# OLD_Motors.net
KiCad netlist of a schematic drawn in Altium Designer
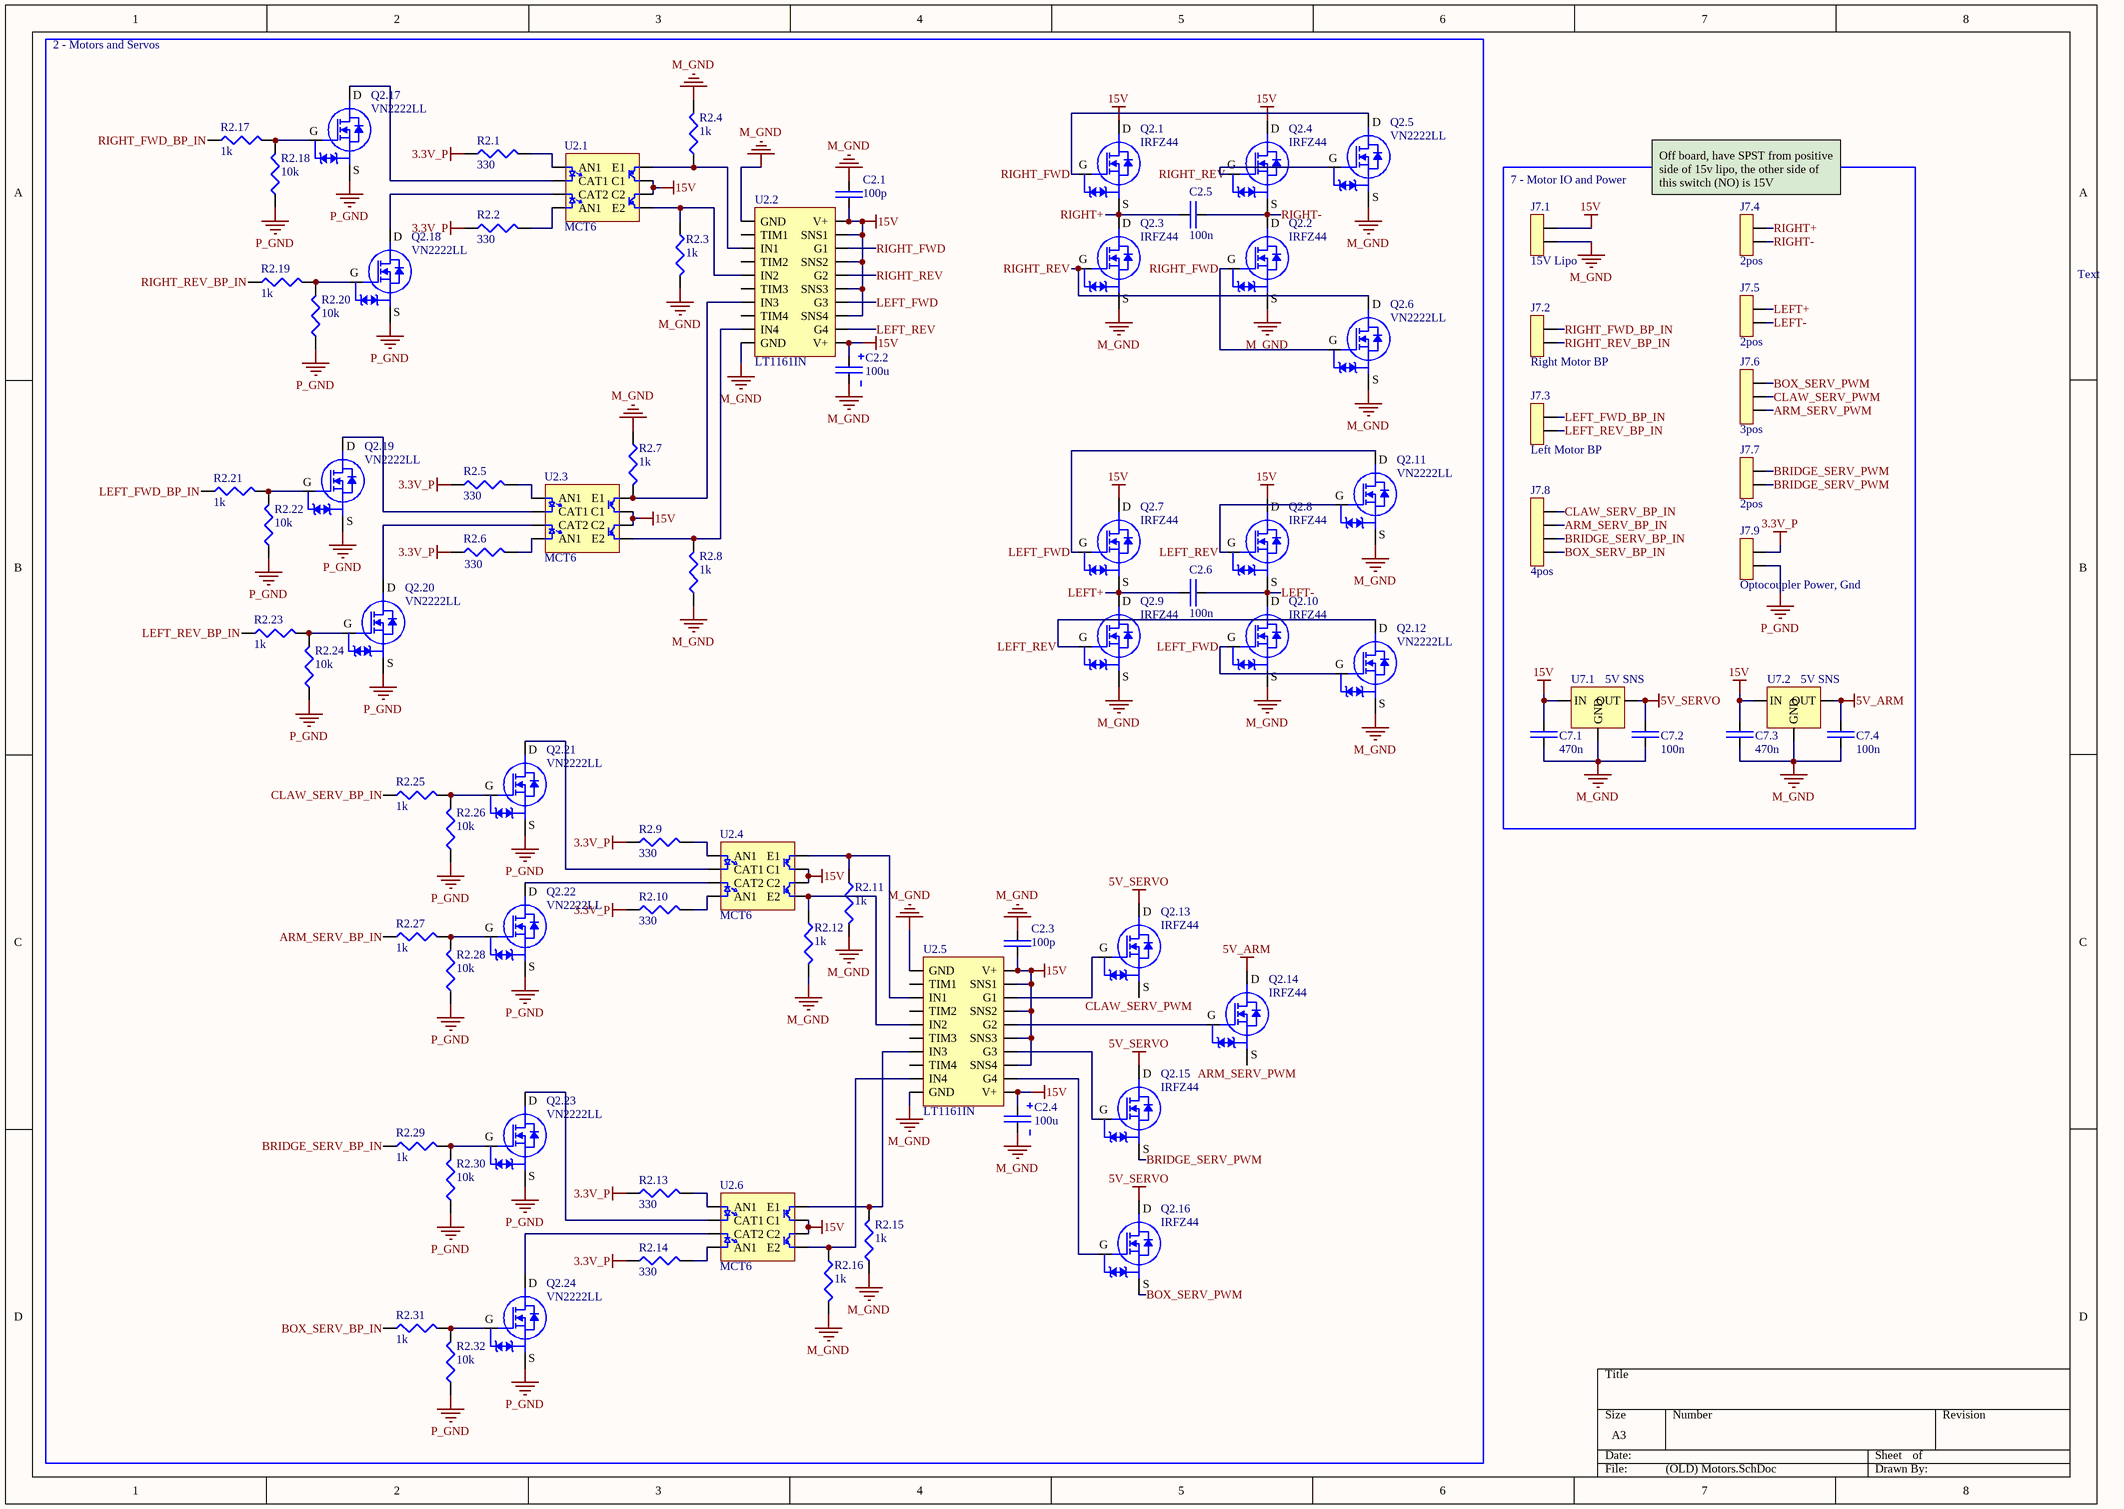
[diagram p0: (OLD) Motors.SchDoc]

(export (version "E")
  (design (tool "Eeschema 10.0.6"))
  (components
    (comp (ref "C2.1")
      (value "100p")
      (footprint "Non Polarized Cap")
      (libsource (lib "SPICEBot_SchLib") (part "Cap_Generic"))
    )
    (comp (ref "C2.2")
      (value "100u")
      (footprint "Polarized Cap")
      (libsource (lib "SPICEBot_SchLib") (part "Polarized Cap"))
    )
    (comp (ref "C2.3")
      (value "100p")
      (footprint "Non Polarized Cap")
      (libsource (lib "SPICEBot_SchLib") (part "Cap_Generic"))
    )
    (comp (ref "C2.4")
      (value "100u")
      (footprint "Polarized Cap")
      (libsource (lib "SPICEBot_SchLib") (part "Polarized Cap"))
    )
    (comp (ref "C2.5")
      (value "100n")
      (footprint "Non Polarized Cap")
      (libsource (lib "SPICEBot_SchLib") (part "Cap_Generic"))
    )
    (comp (ref "C2.6")
      (value "100n")
      (footprint "Non Polarized Cap")
      (libsource (lib "SPICEBot_SchLib") (part "Cap_Generic"))
    )
    (comp (ref "C7.1")
      (value "470n")
      (footprint "Non Polarized Cap")
      (libsource (lib "SPICEBot_SchLib") (part "Cap_Generic"))
    )
    (comp (ref "C7.2")
      (value "100n")
      (footprint "Non Polarized Cap")
      (libsource (lib "SPICEBot_SchLib") (part "Cap_Generic"))
    )
    (comp (ref "C7.3")
      (value "470n")
      (footprint "Non Polarized Cap")
      (libsource (lib "SPICEBot_SchLib") (part "Cap_Generic"))
    )
    (comp (ref "C7.4")
      (value "100n")
      (footprint "Non Polarized Cap")
      (libsource (lib "SPICEBot_SchLib") (part "Cap_Generic"))
    )
    (comp (ref "J7.1")
      (value "15V Lipo")
      (footprint "2pos JST")
      (description "2pos Conn JST")
      (libsource (lib "SPICEBot_SchLib") (part "2pos Conn"))
    )
    (comp (ref "J7.2")
      (value "Right Motor BP")
      (footprint "2pos JST")
      (description "2pos Conn JST")
      (libsource (lib "SPICEBot_SchLib") (part "2pos Conn"))
    )
    (comp (ref "J7.3")
      (value "Left Motor BP")
      (footprint "2pos JST")
      (description "2pos Conn JST")
      (libsource (lib "SPICEBot_SchLib") (part "2pos Conn"))
    )
    (comp (ref "J7.4")
      (value "2pos")
      (footprint "2pos JST")
      (description "2pos Conn JST")
      (libsource (lib "SPICEBot_SchLib") (part "2pos Conn"))
    )
    (comp (ref "J7.5")
      (value "2pos")
      (footprint "2pos JST")
      (description "2pos Conn JST")
      (libsource (lib "SPICEBot_SchLib") (part "2pos Conn"))
    )
    (comp (ref "J7.6")
      (value "3pos")
      (footprint "3pos JST")
      (description "3pos Conn")
      (libsource (lib "SPICEBot_SchLib") (part "3pos Conn"))
    )
    (comp (ref "J7.7")
      (value "2pos")
      (footprint "2pos JST")
      (description "2pos Conn JST")
      (libsource (lib "SPICEBot_SchLib") (part "2pos Conn"))
    )
    (comp (ref "J7.8")
      (value "4pos")
      (footprint "4Pos JST")
      (description "4pos Conn")
      (libsource (lib "SPICEBot_SchLib") (part "4pos Conn"))
    )
    (comp (ref "J7.9")
      (value "Optocoupler Power, Gnd")
      (footprint "2pos JST")
      (description "2pos Conn JST")
      (libsource (lib "SPICEBot_SchLib") (part "2pos Conn"))
    )
    (comp (ref "Q2.1")
      (value "IRFZ44")
      (footprint "TO220")
      (description "IRFZ44EPBF N-Channel 60 V 48A 110W Through Hole TO-220AB")
      (libsource (lib "SPICEBot_SchLib") (part "IRFZ44 NMOS"))
    )
    (comp (ref "Q2.2")
      (value "IRFZ44")
      (footprint "TO220")
      (description "IRFZ44EPBF N-Channel 60 V 48A 110W Through Hole TO-220AB")
      (libsource (lib "SPICEBot_SchLib") (part "IRFZ44 NMOS"))
    )
    (comp (ref "Q2.3")
      (value "IRFZ44")
      (footprint "TO220")
      (description "IRFZ44EPBF N-Channel 60 V 48A 110W Through Hole TO-220AB")
      (libsource (lib "SPICEBot_SchLib") (part "IRFZ44 NMOS"))
    )
    (comp (ref "Q2.4")
      (value "IRFZ44")
      (footprint "TO220")
      (description "IRFZ44EPBF N-Channel 60 V 48A 110W Through Hole TO-220AB")
      (libsource (lib "SPICEBot_SchLib") (part "IRFZ44 NMOS"))
    )
    (comp (ref "Q2.5")
      (value "VN2222LL")
      (footprint "VN2222LL")
      (description "VN2222LL N-Channel 60 V 150mA 400mW Through Hole TO-92 (TO-226)")
      (libsource (lib "SPICEBot_SchLib") (part "VN2222LL NMOS"))
    )
    (comp (ref "Q2.6")
      (value "VN2222LL")
      (footprint "VN2222LL")
      (description "VN2222LL N-Channel 60 V 150mA 400mW Through Hole TO-92 (TO-226)")
      (libsource (lib "SPICEBot_SchLib") (part "VN2222LL NMOS"))
    )
    (comp (ref "Q2.7")
      (value "IRFZ44")
      (footprint "TO220")
      (description "IRFZ44EPBF N-Channel 60 V 48A 110W Through Hole TO-220AB")
      (libsource (lib "SPICEBot_SchLib") (part "IRFZ44 NMOS"))
    )
    (comp (ref "Q2.8")
      (value "IRFZ44")
      (footprint "TO220")
      (description "IRFZ44EPBF N-Channel 60 V 48A 110W Through Hole TO-220AB")
      (libsource (lib "SPICEBot_SchLib") (part "IRFZ44 NMOS"))
    )
    (comp (ref "Q2.9")
      (value "IRFZ44")
      (footprint "TO220")
      (description "IRFZ44EPBF N-Channel 60 V 48A 110W Through Hole TO-220AB")
      (libsource (lib "SPICEBot_SchLib") (part "IRFZ44 NMOS"))
    )
    (comp (ref "Q2.10")
      (value "IRFZ44")
      (footprint "TO220")
      (description "IRFZ44EPBF N-Channel 60 V 48A 110W Through Hole TO-220AB")
      (libsource (lib "SPICEBot_SchLib") (part "IRFZ44 NMOS"))
    )
    (comp (ref "Q2.11")
      (value "VN2222LL")
      (footprint "VN2222LL")
      (description "VN2222LL N-Channel 60 V 150mA 400mW Through Hole TO-92 (TO-226)")
      (libsource (lib "SPICEBot_SchLib") (part "VN2222LL NMOS"))
    )
    (comp (ref "Q2.12")
      (value "VN2222LL")
      (footprint "VN2222LL")
      (description "VN2222LL N-Channel 60 V 150mA 400mW Through Hole TO-92 (TO-226)")
      (libsource (lib "SPICEBot_SchLib") (part "VN2222LL NMOS"))
    )
    (comp (ref "Q2.13")
      (value "IRFZ44")
      (footprint "TO220")
      (description "IRFZ44EPBF N-Channel 60 V 48A 110W Through Hole TO-220AB")
      (libsource (lib "SPICEBot_SchLib") (part "IRFZ44 NMOS"))
    )
    (comp (ref "Q2.14")
      (value "IRFZ44")
      (footprint "TO220")
      (description "IRFZ44EPBF N-Channel 60 V 48A 110W Through Hole TO-220AB")
      (libsource (lib "SPICEBot_SchLib") (part "IRFZ44 NMOS"))
    )
    (comp (ref "Q2.15")
      (value "IRFZ44")
      (footprint "TO220")
      (description "IRFZ44EPBF N-Channel 60 V 48A 110W Through Hole TO-220AB")
      (libsource (lib "SPICEBot_SchLib") (part "IRFZ44 NMOS"))
    )
    (comp (ref "Q2.16")
      (value "IRFZ44")
      (footprint "TO220")
      (description "IRFZ44EPBF N-Channel 60 V 48A 110W Through Hole TO-220AB")
      (libsource (lib "SPICEBot_SchLib") (part "IRFZ44 NMOS"))
    )
    (comp (ref "Q2.17")
      (value "VN2222LL")
      (footprint "VN2222LL")
      (description "VN2222LL N-Channel 60 V 150mA 400mW Through Hole TO-92 (TO-226)")
      (libsource (lib "SPICEBot_SchLib") (part "VN2222LL NMOS"))
    )
    (comp (ref "Q2.18")
      (value "VN2222LL")
      (footprint "VN2222LL")
      (description "VN2222LL N-Channel 60 V 150mA 400mW Through Hole TO-92 (TO-226)")
      (libsource (lib "SPICEBot_SchLib") (part "VN2222LL NMOS"))
    )
    (comp (ref "Q2.19")
      (value "VN2222LL")
      (footprint "VN2222LL")
      (description "VN2222LL N-Channel 60 V 150mA 400mW Through Hole TO-92 (TO-226)")
      (libsource (lib "SPICEBot_SchLib") (part "VN2222LL NMOS"))
    )
    (comp (ref "Q2.20")
      (value "VN2222LL")
      (footprint "VN2222LL")
      (description "VN2222LL N-Channel 60 V 150mA 400mW Through Hole TO-92 (TO-226)")
      (libsource (lib "SPICEBot_SchLib") (part "VN2222LL NMOS"))
    )
    (comp (ref "Q2.21")
      (value "VN2222LL")
      (footprint "VN2222LL")
      (description "VN2222LL N-Channel 60 V 150mA 400mW Through Hole TO-92 (TO-226)")
      (libsource (lib "SPICEBot_SchLib") (part "VN2222LL NMOS"))
    )
    (comp (ref "Q2.22")
      (value "VN2222LL")
      (footprint "VN2222LL")
      (description "VN2222LL N-Channel 60 V 150mA 400mW Through Hole TO-92 (TO-226)")
      (libsource (lib "SPICEBot_SchLib") (part "VN2222LL NMOS"))
    )
    (comp (ref "Q2.23")
      (value "VN2222LL")
      (footprint "VN2222LL")
      (description "VN2222LL N-Channel 60 V 150mA 400mW Through Hole TO-92 (TO-226)")
      (libsource (lib "SPICEBot_SchLib") (part "VN2222LL NMOS"))
    )
    (comp (ref "Q2.24")
      (value "VN2222LL")
      (footprint "VN2222LL")
      (description "VN2222LL N-Channel 60 V 150mA 400mW Through Hole TO-92 (TO-226)")
      (libsource (lib "SPICEBot_SchLib") (part "VN2222LL NMOS"))
    )
    (comp (ref "R2.1")
      (value "330")
      (footprint "Res_Generic")
      (libsource (lib "SPICEBot_SchLib") (part "Res_Generic"))
    )
    (comp (ref "R2.2")
      (value "330")
      (footprint "Res_Generic")
      (libsource (lib "SPICEBot_SchLib") (part "Res_Generic"))
    )
    (comp (ref "R2.3")
      (value "1k")
      (footprint "Res_Generic")
      (libsource (lib "SPICEBot_SchLib") (part "Res_Generic"))
    )
    (comp (ref "R2.4")
      (value "1k")
      (footprint "Res_Generic")
      (libsource (lib "SPICEBot_SchLib") (part "Res_Generic"))
    )
    (comp (ref "R2.5")
      (value "330")
      (footprint "Res_Generic")
      (libsource (lib "SPICEBot_SchLib") (part "Res_Generic"))
    )
    (comp (ref "R2.6")
      (value "330")
      (footprint "Res_Generic")
      (libsource (lib "SPICEBot_SchLib") (part "Res_Generic"))
    )
    (comp (ref "R2.7")
      (value "1k")
      (footprint "Res_Generic")
      (libsource (lib "SPICEBot_SchLib") (part "Res_Generic"))
    )
    (comp (ref "R2.8")
      (value "1k")
      (footprint "Res_Generic")
      (libsource (lib "SPICEBot_SchLib") (part "Res_Generic"))
    )
    (comp (ref "R2.9")
      (value "330")
      (footprint "Res_Generic")
      (libsource (lib "SPICEBot_SchLib") (part "Res_Generic"))
    )
    (comp (ref "R2.10")
      (value "330")
      (footprint "Res_Generic")
      (libsource (lib "SPICEBot_SchLib") (part "Res_Generic"))
    )
    (comp (ref "R2.11")
      (value "1k")
      (footprint "Res_Generic")
      (libsource (lib "SPICEBot_SchLib") (part "Res_Generic"))
    )
    (comp (ref "R2.12")
      (value "1k")
      (footprint "Res_Generic")
      (libsource (lib "SPICEBot_SchLib") (part "Res_Generic"))
    )
    (comp (ref "R2.13")
      (value "330")
      (footprint "Res_Generic")
      (libsource (lib "SPICEBot_SchLib") (part "Res_Generic"))
    )
    (comp (ref "R2.14")
      (value "330")
      (footprint "Res_Generic")
      (libsource (lib "SPICEBot_SchLib") (part "Res_Generic"))
    )
    (comp (ref "R2.15")
      (value "1k")
      (footprint "Res_Generic")
      (libsource (lib "SPICEBot_SchLib") (part "Res_Generic"))
    )
    (comp (ref "R2.16")
      (value "1k")
      (footprint "Res_Generic")
      (libsource (lib "SPICEBot_SchLib") (part "Res_Generic"))
    )
    (comp (ref "R2.17")
      (value "1k")
      (footprint "Res_Generic")
      (libsource (lib "SPICEBot_SchLib") (part "Res_Generic"))
    )
    (comp (ref "R2.18")
      (value "10k")
      (footprint "Res_Generic")
      (libsource (lib "SPICEBot_SchLib") (part "Res_Generic"))
    )
    (comp (ref "R2.19")
      (value "1k")
      (footprint "Res_Generic")
      (libsource (lib "SPICEBot_SchLib") (part "Res_Generic"))
    )
    (comp (ref "R2.20")
      (value "10k")
      (footprint "Res_Generic")
      (libsource (lib "SPICEBot_SchLib") (part "Res_Generic"))
    )
    (comp (ref "R2.21")
      (value "1k")
      (footprint "Res_Generic")
      (libsource (lib "SPICEBot_SchLib") (part "Res_Generic"))
    )
    (comp (ref "R2.22")
      (value "10k")
      (footprint "Res_Generic")
      (libsource (lib "SPICEBot_SchLib") (part "Res_Generic"))
    )
    (comp (ref "R2.23")
      (value "1k")
      (footprint "Res_Generic")
      (libsource (lib "SPICEBot_SchLib") (part "Res_Generic"))
    )
    (comp (ref "R2.24")
      (value "10k")
      (footprint "Res_Generic")
      (libsource (lib "SPICEBot_SchLib") (part "Res_Generic"))
    )
    (comp (ref "R2.25")
      (value "1k")
      (footprint "Res_Generic")
      (libsource (lib "SPICEBot_SchLib") (part "Res_Generic"))
    )
    (comp (ref "R2.26")
      (value "10k")
      (footprint "Res_Generic")
      (libsource (lib "SPICEBot_SchLib") (part "Res_Generic"))
    )
    (comp (ref "R2.27")
      (value "1k")
      (footprint "Res_Generic")
      (libsource (lib "SPICEBot_SchLib") (part "Res_Generic"))
    )
    (comp (ref "R2.28")
      (value "10k")
      (footprint "Res_Generic")
      (libsource (lib "SPICEBot_SchLib") (part "Res_Generic"))
    )
    (comp (ref "R2.29")
      (value "1k")
      (footprint "Res_Generic")
      (libsource (lib "SPICEBot_SchLib") (part "Res_Generic"))
    )
    (comp (ref "R2.30")
      (value "10k")
      (footprint "Res_Generic")
      (libsource (lib "SPICEBot_SchLib") (part "Res_Generic"))
    )
    (comp (ref "R2.31")
      (value "1k")
      (footprint "Res_Generic")
      (libsource (lib "SPICEBot_SchLib") (part "Res_Generic"))
    )
    (comp (ref "R2.32")
      (value "10k")
      (footprint "Res_Generic")
      (libsource (lib "SPICEBot_SchLib") (part "Res_Generic"))
    )
    (comp (ref "U2.1")
      (value "MCT6")
      (footprint "DIP8")
      (description "Optoisolator 5.3KV 2CH TRANS 8-DIP")
      (libsource (lib "SPICEBot_SchLib") (part "MCT6 Optocoupler"))
    )
    (comp (ref "U2.2")
      (value "LT1161IN")
      (footprint "DIP20")
      (description "LT1161IN High-Side Gate Driver IC Non-Inverting 20-PDIP")
      (libsource (lib "SPICEBot_SchLib") (part "LT1161IN Gate Driver"))
    )
    (comp (ref "U2.3")
      (value "MCT6")
      (footprint "DIP8")
      (description "Optoisolator 5.3KV 2CH TRANS 8-DIP")
      (libsource (lib "SPICEBot_SchLib") (part "MCT6 Optocoupler"))
    )
    (comp (ref "U2.4")
      (value "MCT6")
      (footprint "DIP8")
      (description "Optoisolator 5.3KV 2CH TRANS 8-DIP")
      (libsource (lib "SPICEBot_SchLib") (part "MCT6 Optocoupler"))
    )
    (comp (ref "U2.5")
      (value "LT1161IN")
      (footprint "DIP20")
      (description "LT1161IN High-Side Gate Driver IC Non-Inverting 20-PDIP")
      (libsource (lib "SPICEBot_SchLib") (part "LT1161IN Gate Driver"))
    )
    (comp (ref "U2.6")
      (value "MCT6")
      (footprint "DIP8")
      (description "Optoisolator 5.3KV 2CH TRANS 8-DIP")
      (libsource (lib "SPICEBot_SchLib") (part "MCT6 Optocoupler"))
    )
    (comp (ref "U7.1")
      (value "5V SNS")
      (footprint "TO220")
      (description "UA7805 IC REG LINEAR 5V 1.5A TO220-3")
      (libsource (lib "SPICEBot_SchLib") (part "UA7805 5V Reg"))
    )
    (comp (ref "U7.2")
      (value "5V SNS")
      (footprint "TO220")
      (description "UA7805 IC REG LINEAR 5V 1.5A TO220-3")
      (libsource (lib "SPICEBot_SchLib") (part "UA7805 5V Reg"))
    )
  )
  (nets
    (net (code "1") (name "/ARM_SERV_BP_IN") (class "Default")
      (node (ref "J7.8") (pin "3") (pinfunction "3_3") (pintype "passive"))
      (node (ref "R2.27") (pin "1") (pinfunction "1_1") (pintype "passive"))
    )
    (net (code "2") (name "/ARM_SERV_PWM") (class "Default")
      (node (ref "J7.6") (pin "1") (pinfunction "1_1") (pintype "passive"))
      (node (ref "Q2.14") (pin "2") (pinfunction "S_2") (pintype "passive"))
    )
    (net (code "3") (name "/BOX_SERV_BP_IN") (class "Default")
      (node (ref "J7.8") (pin "1") (pinfunction "1_1") (pintype "passive"))
      (node (ref "R2.31") (pin "1") (pinfunction "1_1") (pintype "passive"))
    )
    (net (code "4") (name "/BOX_SERV_PWM") (class "Default")
      (node (ref "J7.6") (pin "3") (pinfunction "3_3") (pintype "passive"))
      (node (ref "Q2.16") (pin "2") (pinfunction "S_2") (pintype "passive"))
    )
    (net (code "5") (name "/BRIDGE_SERV_BP_IN") (class "Default")
      (node (ref "J7.8") (pin "2") (pinfunction "2_2") (pintype "passive"))
      (node (ref "R2.29") (pin "1") (pinfunction "1_1") (pintype "passive"))
    )
    (net (code "6") (name "/BRIDGE_SERV_PWM") (class "Default")
      (node (ref "J7.7") (pin "1") (pinfunction "1_1") (pintype "passive"))
      (node (ref "J7.7") (pin "2") (pinfunction "2_2") (pintype "passive"))
      (node (ref "Q2.15") (pin "2") (pinfunction "S_2") (pintype "passive"))
    )
    (net (code "7") (name "/CLAW_SERV_BP_IN") (class "Default")
      (node (ref "J7.8") (pin "4") (pinfunction "4_4") (pintype "passive"))
      (node (ref "R2.25") (pin "1") (pinfunction "1_1") (pintype "passive"))
    )
    (net (code "8") (name "/CLAW_SERV_PWM") (class "Default")
      (node (ref "J7.6") (pin "2") (pinfunction "2_2") (pintype "passive"))
      (node (ref "Q2.13") (pin "2") (pinfunction "S_2") (pintype "passive"))
    )
    (net (code "9") (name "/LEFT+") (class "Default")
      (node (ref "C2.6") (pin "1") (pinfunction "1_1") (pintype "passive"))
      (node (ref "J7.5") (pin "2") (pinfunction "2_2") (pintype "passive"))
      (node (ref "Q2.7") (pin "2") (pinfunction "S_2") (pintype "passive"))
      (node (ref "Q2.9") (pin "3") (pinfunction "D_3") (pintype "passive"))
    )
    (net (code "10") (name "/LEFT-") (class "Default")
      (node (ref "C2.6") (pin "2") (pinfunction "2_2") (pintype "passive"))
      (node (ref "J7.5") (pin "1") (pinfunction "1_1") (pintype "passive"))
      (node (ref "Q2.10") (pin "3") (pinfunction "D_3") (pintype "passive"))
      (node (ref "Q2.8") (pin "2") (pinfunction "S_2") (pintype "passive"))
    )
    (net (code "11") (name "/LEFT_FWD") (class "Default")
      (node (ref "Q2.10") (pin "1") (pinfunction "G_1") (pintype "passive"))
      (node (ref "Q2.11") (pin "3") (pinfunction "D_3") (pintype "passive"))
      (node (ref "Q2.12") (pin "1") (pinfunction "G_1") (pintype "passive"))
      (node (ref "Q2.7") (pin "1") (pinfunction "G_1") (pintype "passive"))
      (node (ref "U2.2") (pin "14") (pinfunction "G3_14") (pintype "passive"))
    )
    (net (code "12") (name "/LEFT_FWD_BP_IN") (class "Default")
      (node (ref "J7.3") (pin "2") (pinfunction "2_2") (pintype "passive"))
      (node (ref "R2.21") (pin "1") (pinfunction "1_1") (pintype "passive"))
    )
    (net (code "13") (name "/LEFT_REV") (class "Default")
      (node (ref "Q2.11") (pin "1") (pinfunction "G_1") (pintype "passive"))
      (node (ref "Q2.12") (pin "3") (pinfunction "D_3") (pintype "passive"))
      (node (ref "Q2.8") (pin "1") (pinfunction "G_1") (pintype "passive"))
      (node (ref "Q2.9") (pin "1") (pinfunction "G_1") (pintype "passive"))
      (node (ref "U2.2") (pin "12") (pinfunction "G4_12") (pintype "passive"))
    )
    (net (code "14") (name "/LEFT_REV_BP_IN") (class "Default")
      (node (ref "J7.3") (pin "1") (pinfunction "1_1") (pintype "passive"))
      (node (ref "R2.23") (pin "1") (pinfunction "1_1") (pintype "passive"))
    )
    (net (code "15") (name "/RIGHT+") (class "Default")
      (node (ref "C2.5") (pin "1") (pinfunction "1_1") (pintype "passive"))
      (node (ref "J7.4") (pin "2") (pinfunction "2_2") (pintype "passive"))
      (node (ref "Q2.1") (pin "2") (pinfunction "S_2") (pintype "passive"))
      (node (ref "Q2.3") (pin "3") (pinfunction "D_3") (pintype "passive"))
    )
    (net (code "16") (name "/RIGHT-") (class "Default")
      (node (ref "C2.5") (pin "2") (pinfunction "2_2") (pintype "passive"))
      (node (ref "J7.4") (pin "1") (pinfunction "1_1") (pintype "passive"))
      (node (ref "Q2.2") (pin "3") (pinfunction "D_3") (pintype "passive"))
      (node (ref "Q2.4") (pin "2") (pinfunction "S_2") (pintype "passive"))
    )
    (net (code "17") (name "/RIGHT_FWD") (class "Default")
      (node (ref "Q2.1") (pin "1") (pinfunction "G_1") (pintype "passive"))
      (node (ref "Q2.2") (pin "1") (pinfunction "G_1") (pintype "passive"))
      (node (ref "Q2.5") (pin "3") (pinfunction "D_3") (pintype "passive"))
      (node (ref "Q2.6") (pin "1") (pinfunction "G_1") (pintype "passive"))
      (node (ref "U2.2") (pin "18") (pinfunction "G1_18") (pintype "passive"))
    )
    (net (code "18") (name "/RIGHT_FWD_BP_IN") (class "Default")
      (node (ref "J7.2") (pin "2") (pinfunction "2_2") (pintype "passive"))
      (node (ref "R2.17") (pin "1") (pinfunction "1_1") (pintype "passive"))
    )
    (net (code "19") (name "/RIGHT_REV") (class "Default")
      (node (ref "Q2.3") (pin "1") (pinfunction "G_1") (pintype "passive"))
      (node (ref "Q2.4") (pin "1") (pinfunction "G_1") (pintype "passive"))
      (node (ref "Q2.5") (pin "1") (pinfunction "G_1") (pintype "passive"))
      (node (ref "Q2.6") (pin "3") (pinfunction "D_3") (pintype "passive"))
      (node (ref "U2.2") (pin "16") (pinfunction "G2_16") (pintype "passive"))
    )
    (net (code "20") (name "/RIGHT_REV_BP_IN") (class "Default")
      (node (ref "J7.2") (pin "1") (pinfunction "1_1") (pintype "passive"))
      (node (ref "R2.19") (pin "1") (pinfunction "1_1") (pintype "passive"))
    )
    (net (code "21") (name "3.3V_P") (class "Default")
      (node (ref "J7.9") (pin "2") (pinfunction "2_2") (pintype "passive"))
      (node (ref "R2.1") (pin "1") (pinfunction "1_1") (pintype "passive"))
      (node (ref "R2.10") (pin "1") (pinfunction "1_1") (pintype "passive"))
      (node (ref "R2.13") (pin "1") (pinfunction "1_1") (pintype "passive"))
      (node (ref "R2.14") (pin "1") (pinfunction "1_1") (pintype "passive"))
      (node (ref "R2.2") (pin "1") (pinfunction "1_1") (pintype "passive"))
      (node (ref "R2.5") (pin "1") (pinfunction "1_1") (pintype "passive"))
      (node (ref "R2.6") (pin "1") (pinfunction "1_1") (pintype "passive"))
      (node (ref "R2.9") (pin "1") (pinfunction "1_1") (pintype "passive"))
    )
    (net (code "22") (name "5V_ARM") (class "Default")
      (node (ref "C7.4") (pin "2") (pinfunction "2_2") (pintype "passive"))
      (node (ref "Q2.14") (pin "3") (pinfunction "D_3") (pintype "passive"))
      (node (ref "U7.2") (pin "3") (pinfunction "OUT_3") (pintype "passive"))
    )
    (net (code "23") (name "5V_SERVO") (class "Default")
      (node (ref "C7.2") (pin "2") (pinfunction "2_2") (pintype "passive"))
      (node (ref "Q2.13") (pin "3") (pinfunction "D_3") (pintype "passive"))
      (node (ref "Q2.15") (pin "3") (pinfunction "D_3") (pintype "passive"))
      (node (ref "Q2.16") (pin "3") (pinfunction "D_3") (pintype "passive"))
      (node (ref "U7.1") (pin "3") (pinfunction "OUT_3") (pintype "passive"))
    )
    (net (code "24") (name "15V") (class "Default")
      (node (ref "C2.1") (pin "1") (pinfunction "1_1") (pintype "passive"))
      (node (ref "C2.2") (pin "1") (pinfunction "1_1") (pintype "passive"))
      (node (ref "C2.3") (pin "1") (pinfunction "1_1") (pintype "passive"))
      (node (ref "C2.4") (pin "1") (pinfunction "1_1") (pintype "passive"))
      (node (ref "C7.1") (pin "2") (pinfunction "2_2") (pintype "passive"))
      (node (ref "C7.3") (pin "2") (pinfunction "2_2") (pintype "passive"))
      (node (ref "J7.1") (pin "2") (pinfunction "2_2") (pintype "passive"))
      (node (ref "Q2.1") (pin "3") (pinfunction "D_3") (pintype "passive"))
      (node (ref "Q2.4") (pin "3") (pinfunction "D_3") (pintype "passive"))
      (node (ref "Q2.7") (pin "3") (pinfunction "D_3") (pintype "passive"))
      (node (ref "Q2.8") (pin "3") (pinfunction "D_3") (pintype "passive"))
      (node (ref "U2.1") (pin "6") (pinfunction "C2_6") (pintype "passive"))
      (node (ref "U2.1") (pin "7") (pinfunction "C1_7") (pintype "passive"))
      (node (ref "U2.2") (pin "11") (pinfunction "V+_11") (pintype "passive"))
      (node (ref "U2.2") (pin "13") (pinfunction "SNS4_13") (pintype "passive"))
      (node (ref "U2.2") (pin "15") (pinfunction "SNS3_15") (pintype "passive"))
      (node (ref "U2.2") (pin "17") (pinfunction "SNS2_17") (pintype "passive"))
      (node (ref "U2.2") (pin "19") (pinfunction "SNS1_19") (pintype "passive"))
      (node (ref "U2.2") (pin "20") (pinfunction "V+_20") (pintype "passive"))
      (node (ref "U2.3") (pin "6") (pinfunction "C2_6") (pintype "passive"))
      (node (ref "U2.3") (pin "7") (pinfunction "C1_7") (pintype "passive"))
      (node (ref "U2.4") (pin "6") (pinfunction "C2_6") (pintype "passive"))
      (node (ref "U2.4") (pin "7") (pinfunction "C1_7") (pintype "passive"))
      (node (ref "U2.5") (pin "11") (pinfunction "V+_11") (pintype "passive"))
      (node (ref "U2.5") (pin "13") (pinfunction "SNS4_13") (pintype "passive"))
      (node (ref "U2.5") (pin "15") (pinfunction "SNS3_15") (pintype "passive"))
      (node (ref "U2.5") (pin "17") (pinfunction "SNS2_17") (pintype "passive"))
      (node (ref "U2.5") (pin "19") (pinfunction "SNS1_19") (pintype "passive"))
      (node (ref "U2.5") (pin "20") (pinfunction "V+_20") (pintype "passive"))
      (node (ref "U2.6") (pin "6") (pinfunction "C2_6") (pintype "passive"))
      (node (ref "U2.6") (pin "7") (pinfunction "C1_7") (pintype "passive"))
      (node (ref "U7.1") (pin "1") (pinfunction "IN_1") (pintype "passive"))
      (node (ref "U7.2") (pin "1") (pinfunction "IN_1") (pintype "passive"))
    )
    (net (code "25") (name "M_GND") (class "Default")
      (node (ref "C2.1") (pin "2") (pinfunction "2_2") (pintype "passive"))
      (node (ref "C2.2") (pin "2") (pinfunction "2_2") (pintype "passive"))
      (node (ref "C2.3") (pin "2") (pinfunction "2_2") (pintype "passive"))
      (node (ref "C2.4") (pin "2") (pinfunction "2_2") (pintype "passive"))
      (node (ref "C7.1") (pin "1") (pinfunction "1_1") (pintype "passive"))
      (node (ref "C7.2") (pin "1") (pinfunction "1_1") (pintype "passive"))
      (node (ref "C7.3") (pin "1") (pinfunction "1_1") (pintype "passive"))
      (node (ref "C7.4") (pin "1") (pinfunction "1_1") (pintype "passive"))
      (node (ref "J7.1") (pin "1") (pinfunction "1_1") (pintype "passive"))
      (node (ref "Q2.10") (pin "2") (pinfunction "S_2") (pintype "passive"))
      (node (ref "Q2.11") (pin "2") (pinfunction "S_2") (pintype "passive"))
      (node (ref "Q2.12") (pin "2") (pinfunction "S_2") (pintype "passive"))
      (node (ref "Q2.2") (pin "2") (pinfunction "S_2") (pintype "passive"))
      (node (ref "Q2.3") (pin "2") (pinfunction "S_2") (pintype "passive"))
      (node (ref "Q2.5") (pin "2") (pinfunction "S_2") (pintype "passive"))
      (node (ref "Q2.6") (pin "2") (pinfunction "S_2") (pintype "passive"))
      (node (ref "Q2.9") (pin "2") (pinfunction "S_2") (pintype "passive"))
      (node (ref "R2.11") (pin "2") (pinfunction "2_2") (pintype "passive"))
      (node (ref "R2.12") (pin "2") (pinfunction "2_2") (pintype "passive"))
      (node (ref "R2.15") (pin "1") (pinfunction "1_1") (pintype "passive"))
      (node (ref "R2.16") (pin "2") (pinfunction "2_2") (pintype "passive"))
      (node (ref "R2.3") (pin "2") (pinfunction "2_2") (pintype "passive"))
      (node (ref "R2.4") (pin "2") (pinfunction "2_2") (pintype "passive"))
      (node (ref "R2.7") (pin "1") (pinfunction "1_1") (pintype "passive"))
      (node (ref "R2.8") (pin "1") (pinfunction "1_1") (pintype "passive"))
      (node (ref "U2.2") (pin "1") (pinfunction "GND_1") (pintype "passive"))
      (node (ref "U2.2") (pin "10") (pinfunction "GND_10") (pintype "passive"))
      (node (ref "U2.5") (pin "1") (pinfunction "GND_1") (pintype "passive"))
      (node (ref "U2.5") (pin "10") (pinfunction "GND_10") (pintype "passive"))
      (node (ref "U7.1") (pin "2") (pinfunction "GND_2") (pintype "passive"))
      (node (ref "U7.2") (pin "2") (pinfunction "GND_2") (pintype "passive"))
    )
    (net (code "26") (name "Net-(Q2.13-G)") (class "Default")
      (node (ref "Q2.13") (pin "1") (pinfunction "G_1") (pintype "passive"))
      (node (ref "U2.5") (pin "18") (pinfunction "G1_18") (pintype "passive"))
    )
    (net (code "27") (name "Net-(Q2.14-G)") (class "Default")
      (node (ref "Q2.14") (pin "1") (pinfunction "G_1") (pintype "passive"))
      (node (ref "U2.5") (pin "16") (pinfunction "G2_16") (pintype "passive"))
    )
    (net (code "28") (name "Net-(Q2.15-G)") (class "Default")
      (node (ref "Q2.15") (pin "1") (pinfunction "G_1") (pintype "passive"))
      (node (ref "U2.5") (pin "14") (pinfunction "G3_14") (pintype "passive"))
    )
    (net (code "29") (name "Net-(Q2.16-G)") (class "Default")
      (node (ref "Q2.16") (pin "1") (pinfunction "G_1") (pintype "passive"))
      (node (ref "U2.5") (pin "12") (pinfunction "G4_12") (pintype "passive"))
    )
    (net (code "30") (name "Net-(Q2.17-D)") (class "Default")
      (node (ref "Q2.17") (pin "3") (pinfunction "D_3") (pintype "passive"))
      (node (ref "U2.1") (pin "2") (pinfunction "CAT1_2") (pintype "passive"))
    )
    (net (code "31") (name "Net-(Q2.17-G)") (class "Default")
      (node (ref "Q2.17") (pin "1") (pinfunction "G_1") (pintype "passive"))
      (node (ref "R2.17") (pin "2") (pinfunction "2_2") (pintype "passive"))
      (node (ref "R2.18") (pin "2") (pinfunction "2_2") (pintype "passive"))
    )
    (net (code "32") (name "Net-(Q2.18-D)") (class "Default")
      (node (ref "Q2.18") (pin "3") (pinfunction "D_3") (pintype "passive"))
      (node (ref "U2.1") (pin "3") (pinfunction "CAT2_3") (pintype "passive"))
    )
    (net (code "33") (name "Net-(Q2.18-G)") (class "Default")
      (node (ref "Q2.18") (pin "1") (pinfunction "G_1") (pintype "passive"))
      (node (ref "R2.19") (pin "2") (pinfunction "2_2") (pintype "passive"))
      (node (ref "R2.20") (pin "2") (pinfunction "2_2") (pintype "passive"))
    )
    (net (code "34") (name "Net-(Q2.19-D)") (class "Default")
      (node (ref "Q2.19") (pin "3") (pinfunction "D_3") (pintype "passive"))
      (node (ref "U2.3") (pin "2") (pinfunction "CAT1_2") (pintype "passive"))
    )
    (net (code "35") (name "Net-(Q2.19-G)") (class "Default")
      (node (ref "Q2.19") (pin "1") (pinfunction "G_1") (pintype "passive"))
      (node (ref "R2.21") (pin "2") (pinfunction "2_2") (pintype "passive"))
      (node (ref "R2.22") (pin "2") (pinfunction "2_2") (pintype "passive"))
    )
    (net (code "36") (name "Net-(Q2.20-D)") (class "Default")
      (node (ref "Q2.20") (pin "3") (pinfunction "D_3") (pintype "passive"))
      (node (ref "U2.3") (pin "3") (pinfunction "CAT2_3") (pintype "passive"))
    )
    (net (code "37") (name "Net-(Q2.20-G)") (class "Default")
      (node (ref "Q2.20") (pin "1") (pinfunction "G_1") (pintype "passive"))
      (node (ref "R2.23") (pin "2") (pinfunction "2_2") (pintype "passive"))
      (node (ref "R2.24") (pin "2") (pinfunction "2_2") (pintype "passive"))
    )
    (net (code "38") (name "Net-(Q2.21-D)") (class "Default")
      (node (ref "Q2.21") (pin "3") (pinfunction "D_3") (pintype "passive"))
      (node (ref "U2.4") (pin "2") (pinfunction "CAT1_2") (pintype "passive"))
    )
    (net (code "39") (name "Net-(Q2.21-G)") (class "Default")
      (node (ref "Q2.21") (pin "1") (pinfunction "G_1") (pintype "passive"))
      (node (ref "R2.25") (pin "2") (pinfunction "2_2") (pintype "passive"))
      (node (ref "R2.26") (pin "2") (pinfunction "2_2") (pintype "passive"))
    )
    (net (code "40") (name "Net-(Q2.22-D)") (class "Default")
      (node (ref "Q2.22") (pin "3") (pinfunction "D_3") (pintype "passive"))
      (node (ref "U2.4") (pin "3") (pinfunction "CAT2_3") (pintype "passive"))
    )
    (net (code "41") (name "Net-(Q2.22-G)") (class "Default")
      (node (ref "Q2.22") (pin "1") (pinfunction "G_1") (pintype "passive"))
      (node (ref "R2.27") (pin "2") (pinfunction "2_2") (pintype "passive"))
      (node (ref "R2.28") (pin "2") (pinfunction "2_2") (pintype "passive"))
    )
    (net (code "42") (name "Net-(Q2.23-D)") (class "Default")
      (node (ref "Q2.23") (pin "3") (pinfunction "D_3") (pintype "passive"))
      (node (ref "U2.6") (pin "2") (pinfunction "CAT1_2") (pintype "passive"))
    )
    (net (code "43") (name "Net-(Q2.23-G)") (class "Default")
      (node (ref "Q2.23") (pin "1") (pinfunction "G_1") (pintype "passive"))
      (node (ref "R2.29") (pin "2") (pinfunction "2_2") (pintype "passive"))
      (node (ref "R2.30") (pin "2") (pinfunction "2_2") (pintype "passive"))
    )
    (net (code "44") (name "Net-(Q2.24-D)") (class "Default")
      (node (ref "Q2.24") (pin "3") (pinfunction "D_3") (pintype "passive"))
      (node (ref "U2.6") (pin "3") (pinfunction "CAT2_3") (pintype "passive"))
    )
    (net (code "45") (name "Net-(Q2.24-G)") (class "Default")
      (node (ref "Q2.24") (pin "1") (pinfunction "G_1") (pintype "passive"))
      (node (ref "R2.31") (pin "2") (pinfunction "2_2") (pintype "passive"))
      (node (ref "R2.32") (pin "2") (pinfunction "2_2") (pintype "passive"))
    )
    (net (code "46") (name "Net-(R2.1-Pad2)") (class "Default")
      (node (ref "R2.1") (pin "2") (pinfunction "2_2") (pintype "passive"))
      (node (ref "U2.1") (pin "1") (pinfunction "AN1_1") (pintype "passive"))
    )
    (net (code "47") (name "Net-(R2.2-Pad2)") (class "Default")
      (node (ref "R2.2") (pin "2") (pinfunction "2_2") (pintype "passive"))
      (node (ref "U2.1") (pin "4") (pinfunction "AN1_4") (pintype "passive"))
    )
    (net (code "48") (name "Net-(R2.5-Pad2)") (class "Default")
      (node (ref "R2.5") (pin "2") (pinfunction "2_2") (pintype "passive"))
      (node (ref "U2.3") (pin "1") (pinfunction "AN1_1") (pintype "passive"))
    )
    (net (code "49") (name "Net-(R2.6-Pad2)") (class "Default")
      (node (ref "R2.6") (pin "2") (pinfunction "2_2") (pintype "passive"))
      (node (ref "U2.3") (pin "4") (pinfunction "AN1_4") (pintype "passive"))
    )
    (net (code "50") (name "Net-(R2.9-Pad2)") (class "Default")
      (node (ref "R2.9") (pin "2") (pinfunction "2_2") (pintype "passive"))
      (node (ref "U2.4") (pin "1") (pinfunction "AN1_1") (pintype "passive"))
    )
    (net (code "51") (name "Net-(R2.10-Pad2)") (class "Default")
      (node (ref "R2.10") (pin "2") (pinfunction "2_2") (pintype "passive"))
      (node (ref "U2.4") (pin "4") (pinfunction "AN1_4") (pintype "passive"))
    )
    (net (code "52") (name "Net-(R2.13-Pad2)") (class "Default")
      (node (ref "R2.13") (pin "2") (pinfunction "2_2") (pintype "passive"))
      (node (ref "U2.6") (pin "1") (pinfunction "AN1_1") (pintype "passive"))
    )
    (net (code "53") (name "Net-(R2.14-Pad2)") (class "Default")
      (node (ref "R2.14") (pin "2") (pinfunction "2_2") (pintype "passive"))
      (node (ref "U2.6") (pin "4") (pinfunction "AN1_4") (pintype "passive"))
    )
    (net (code "54") (name "Net-(U2.1-E1)") (class "Default")
      (node (ref "R2.4") (pin "1") (pinfunction "1_1") (pintype "passive"))
      (node (ref "U2.1") (pin "8") (pinfunction "E1_8") (pintype "passive"))
      (node (ref "U2.2") (pin "3") (pinfunction "IN1_3") (pintype "passive"))
    )
    (net (code "55") (name "Net-(U2.1-E2)") (class "Default")
      (node (ref "R2.3") (pin "1") (pinfunction "1_1") (pintype "passive"))
      (node (ref "U2.1") (pin "5") (pinfunction "E2_5") (pintype "passive"))
      (node (ref "U2.2") (pin "5") (pinfunction "IN2_5") (pintype "passive"))
    )
    (net (code "56") (name "Net-(U2.2-IN3)") (class "Default")
      (node (ref "R2.7") (pin "2") (pinfunction "2_2") (pintype "passive"))
      (node (ref "U2.2") (pin "7") (pinfunction "IN3_7") (pintype "passive"))
      (node (ref "U2.3") (pin "8") (pinfunction "E1_8") (pintype "passive"))
    )
    (net (code "57") (name "Net-(U2.2-IN4)") (class "Default")
      (node (ref "R2.8") (pin "2") (pinfunction "2_2") (pintype "passive"))
      (node (ref "U2.2") (pin "9") (pinfunction "IN4_9") (pintype "passive"))
      (node (ref "U2.3") (pin "5") (pinfunction "E2_5") (pintype "passive"))
    )
    (net (code "58") (name "Net-(U2.4-E1)") (class "Default")
      (node (ref "R2.11") (pin "1") (pinfunction "1_1") (pintype "passive"))
      (node (ref "U2.4") (pin "8") (pinfunction "E1_8") (pintype "passive"))
      (node (ref "U2.5") (pin "3") (pinfunction "IN1_3") (pintype "passive"))
    )
    (net (code "59") (name "Net-(U2.4-E2)") (class "Default")
      (node (ref "R2.12") (pin "1") (pinfunction "1_1") (pintype "passive"))
      (node (ref "U2.4") (pin "5") (pinfunction "E2_5") (pintype "passive"))
      (node (ref "U2.5") (pin "5") (pinfunction "IN2_5") (pintype "passive"))
    )
    (net (code "60") (name "Net-(U2.5-IN3)") (class "Default")
      (node (ref "R2.15") (pin "2") (pinfunction "2_2") (pintype "passive"))
      (node (ref "U2.5") (pin "7") (pinfunction "IN3_7") (pintype "passive"))
      (node (ref "U2.6") (pin "8") (pinfunction "E1_8") (pintype "passive"))
    )
    (net (code "61") (name "Net-(U2.5-IN4)") (class "Default")
      (node (ref "R2.16") (pin "1") (pinfunction "1_1") (pintype "passive"))
      (node (ref "U2.5") (pin "9") (pinfunction "IN4_9") (pintype "passive"))
      (node (ref "U2.6") (pin "5") (pinfunction "E2_5") (pintype "passive"))
    )
    (net (code "62") (name "P_GND") (class "Default")
      (node (ref "J7.9") (pin "1") (pinfunction "1_1") (pintype "passive"))
      (node (ref "Q2.17") (pin "2") (pinfunction "S_2") (pintype "passive"))
      (node (ref "Q2.18") (pin "2") (pinfunction "S_2") (pintype "passive"))
      (node (ref "Q2.19") (pin "2") (pinfunction "S_2") (pintype "passive"))
      (node (ref "Q2.20") (pin "2") (pinfunction "S_2") (pintype "passive"))
      (node (ref "Q2.21") (pin "2") (pinfunction "S_2") (pintype "passive"))
      (node (ref "Q2.22") (pin "2") (pinfunction "S_2") (pintype "passive"))
      (node (ref "Q2.23") (pin "2") (pinfunction "S_2") (pintype "passive"))
      (node (ref "Q2.24") (pin "2") (pinfunction "S_2") (pintype "passive"))
      (node (ref "R2.18") (pin "1") (pinfunction "1_1") (pintype "passive"))
      (node (ref "R2.20") (pin "1") (pinfunction "1_1") (pintype "passive"))
      (node (ref "R2.22") (pin "1") (pinfunction "1_1") (pintype "passive"))
      (node (ref "R2.24") (pin "1") (pinfunction "1_1") (pintype "passive"))
      (node (ref "R2.26") (pin "1") (pinfunction "1_1") (pintype "passive"))
      (node (ref "R2.28") (pin "1") (pinfunction "1_1") (pintype "passive"))
      (node (ref "R2.30") (pin "1") (pinfunction "1_1") (pintype "passive"))
      (node (ref "R2.32") (pin "1") (pinfunction "1_1") (pintype "passive"))
    )
    (net (code "63") (name "unconnected-(U2.2-TIM1-Pad2)") (class "Default")
      (node (ref "U2.2") (pin "2") (pinfunction "TIM1_2") (pintype "passive"))
    )
    (net (code "64") (name "unconnected-(U2.2-TIM2-Pad4)") (class "Default")
      (node (ref "U2.2") (pin "4") (pinfunction "TIM2_4") (pintype "passive"))
    )
    (net (code "65") (name "unconnected-(U2.2-TIM3-Pad6)") (class "Default")
      (node (ref "U2.2") (pin "6") (pinfunction "TIM3_6") (pintype "passive"))
    )
    (net (code "66") (name "unconnected-(U2.2-TIM4-Pad8)") (class "Default")
      (node (ref "U2.2") (pin "8") (pinfunction "TIM4_8") (pintype "passive"))
    )
    (net (code "67") (name "unconnected-(U2.5-TIM1-Pad2)") (class "Default")
      (node (ref "U2.5") (pin "2") (pinfunction "TIM1_2") (pintype "passive"))
    )
    (net (code "68") (name "unconnected-(U2.5-TIM2-Pad4)") (class "Default")
      (node (ref "U2.5") (pin "4") (pinfunction "TIM2_4") (pintype "passive"))
    )
    (net (code "69") (name "unconnected-(U2.5-TIM3-Pad6)") (class "Default")
      (node (ref "U2.5") (pin "6") (pinfunction "TIM3_6") (pintype "passive"))
    )
    (net (code "70") (name "unconnected-(U2.5-TIM4-Pad8)") (class "Default")
      (node (ref "U2.5") (pin "8") (pinfunction "TIM4_8") (pintype "passive"))
    )
  )
)
